# ATtiny20_Study.net
KiCad netlist of a schematic drawn in EAGLE
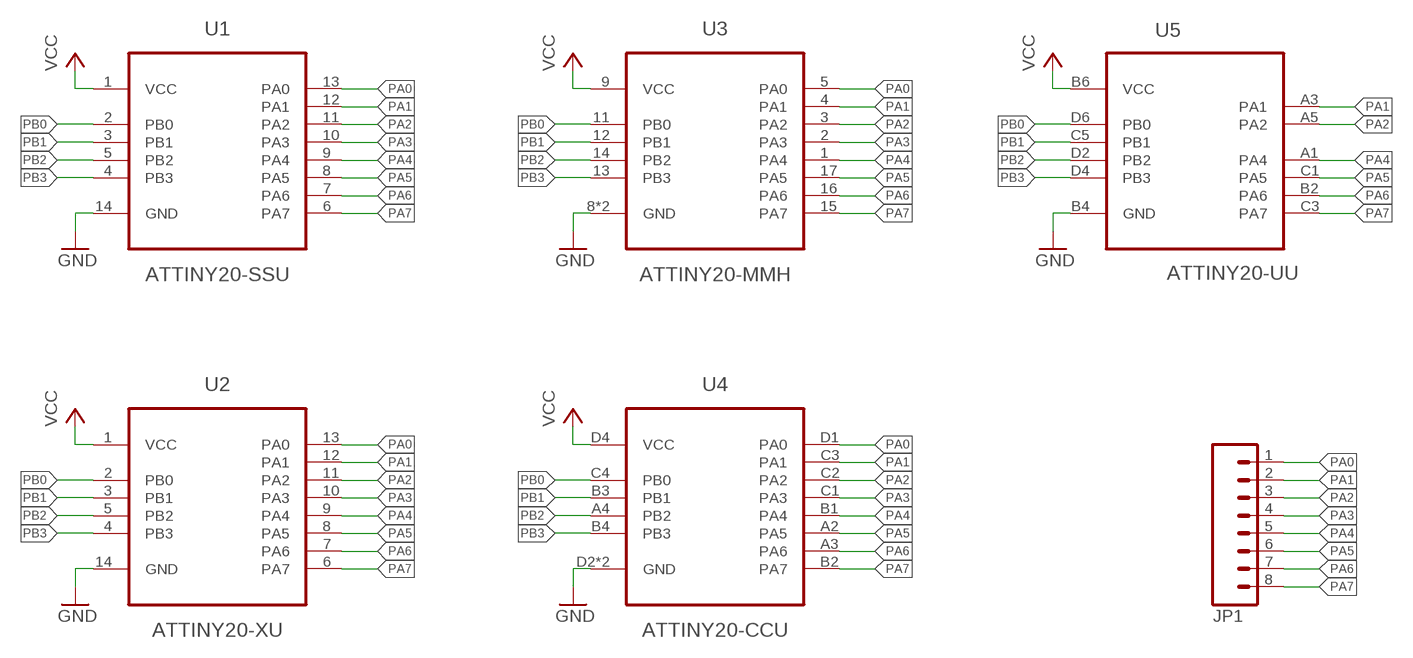
[diagram p0: schematic, sheet 1]

(export (version "E")
  (design (tool "Eeschema 10.0.6"))
  (components
    (comp (ref "JP1")
      (value "M08LOCK_NO_SILK")
      (footprint "eagle-import:1X08_LOCK_NO_SILK")
      (libsource (lib "eagle-import") (part "M08LOCK_NO_SILK"))
    )
    (comp (ref "U1")
      (value "ATTINY20-SSU")
      (footprint "eagle-import:14S1")
      (libsource (lib "eagle-import") (part "ATTINY20-SSU"))
    )
    (comp (ref "U2")
      (value "ATTINY20-XU")
      (footprint "eagle-import:14X")
      (libsource (lib "eagle-import") (part "ATTINY20-XU"))
    )
    (comp (ref "U3")
      (value "ATTINY20-MMH")
      (footprint "eagle-import:20M2")
      (libsource (lib "eagle-import") (part "ATTINY20-MMH"))
    )
    (comp (ref "U4")
      (value "ATTINY20-CCU")
      (footprint "eagle-import:15CC1")
      (libsource (lib "eagle-import") (part "ATTINY20-CCU"))
    )
    (comp (ref "U5")
      (value "ATTINY20-UU")
      (footprint "eagle-import:12U-1")
      (libsource (lib "eagle-import") (part "ATTINY20-UU"))
    )
  )
  (nets
    (net (code "1") (name "GND") (class "Default")
      (node (ref "U1") (pin "14") (pinfunction "GND_14") (pintype "passive"))
      (node (ref "U2") (pin "14") (pinfunction "GND_14") (pintype "passive"))
      (node (ref "U3") (pin "8") (pinfunction "GND_8") (pintype "passive"))
      (node (ref "U3") (pin "PAD") (pinfunction "GND_PAD") (pintype "passive"))
      (node (ref "U4") (pin "D2") (pinfunction "GND_D2") (pintype "passive"))
      (node (ref "U4") (pin "D3") (pinfunction "GND_D3") (pintype "passive"))
      (node (ref "U5") (pin "B4") (pinfunction "GND_B4") (pintype "passive"))
    )
    (net (code "2") (name "PA0") (class "Default")
      (node (ref "JP1") (pin "1") (pinfunction "1_1") (pintype "passive"))
      (node (ref "U1") (pin "13") (pinfunction "PA0_13") (pintype "bidirectional"))
      (node (ref "U2") (pin "13") (pinfunction "PA0_13") (pintype "bidirectional"))
      (node (ref "U3") (pin "5") (pinfunction "PA0_5") (pintype "bidirectional"))
      (node (ref "U4") (pin "D1") (pinfunction "PA0_D1") (pintype "bidirectional"))
    )
    (net (code "3") (name "PA1") (class "Default")
      (node (ref "JP1") (pin "2") (pinfunction "2_2") (pintype "passive"))
      (node (ref "U1") (pin "12") (pinfunction "PA1_12") (pintype "bidirectional"))
      (node (ref "U2") (pin "12") (pinfunction "PA1_12") (pintype "bidirectional"))
      (node (ref "U3") (pin "4") (pinfunction "PA1_4") (pintype "bidirectional"))
      (node (ref "U4") (pin "C3") (pinfunction "PA1_C3") (pintype "bidirectional"))
      (node (ref "U5") (pin "A3") (pinfunction "PA1_A3") (pintype "bidirectional"))
    )
    (net (code "4") (name "PA2") (class "Default")
      (node (ref "JP1") (pin "3") (pinfunction "3_3") (pintype "passive"))
      (node (ref "U1") (pin "11") (pinfunction "PA2_11") (pintype "bidirectional"))
      (node (ref "U2") (pin "11") (pinfunction "PA2_11") (pintype "bidirectional"))
      (node (ref "U3") (pin "3") (pinfunction "PA2_3") (pintype "bidirectional"))
      (node (ref "U4") (pin "C2") (pinfunction "PA2_C2") (pintype "bidirectional"))
      (node (ref "U5") (pin "A5") (pinfunction "PA2_A5") (pintype "bidirectional"))
    )
    (net (code "5") (name "PA3") (class "Default")
      (node (ref "JP1") (pin "4") (pinfunction "4_4") (pintype "passive"))
      (node (ref "U1") (pin "10") (pinfunction "PA3_10") (pintype "bidirectional"))
      (node (ref "U2") (pin "10") (pinfunction "PA3_10") (pintype "bidirectional"))
      (node (ref "U3") (pin "2") (pinfunction "PA3_2") (pintype "bidirectional"))
      (node (ref "U4") (pin "C1") (pinfunction "PA3_C1") (pintype "bidirectional"))
    )
    (net (code "6") (name "PA4") (class "Default")
      (node (ref "JP1") (pin "5") (pinfunction "5_5") (pintype "passive"))
      (node (ref "U1") (pin "9") (pinfunction "PA4_9") (pintype "bidirectional"))
      (node (ref "U2") (pin "9") (pinfunction "PA4_9") (pintype "bidirectional"))
      (node (ref "U3") (pin "1") (pinfunction "PA4_1") (pintype "bidirectional"))
      (node (ref "U4") (pin "B1") (pinfunction "PA4_B1") (pintype "bidirectional"))
      (node (ref "U5") (pin "A1") (pinfunction "PA4_A1") (pintype "bidirectional"))
    )
    (net (code "7") (name "PA5") (class "Default")
      (node (ref "JP1") (pin "6") (pinfunction "6_6") (pintype "passive"))
      (node (ref "U1") (pin "8") (pinfunction "PA5_8") (pintype "bidirectional"))
      (node (ref "U2") (pin "8") (pinfunction "PA5_8") (pintype "bidirectional"))
      (node (ref "U3") (pin "17") (pinfunction "PA5_17") (pintype "bidirectional"))
      (node (ref "U4") (pin "A2") (pinfunction "PA5_A2") (pintype "bidirectional"))
      (node (ref "U5") (pin "C1") (pinfunction "PA5_C1") (pintype "bidirectional"))
    )
    (net (code "8") (name "PA6") (class "Default")
      (node (ref "JP1") (pin "7") (pinfunction "7_7") (pintype "passive"))
      (node (ref "U1") (pin "7") (pinfunction "PA6_7") (pintype "bidirectional"))
      (node (ref "U2") (pin "7") (pinfunction "PA6_7") (pintype "bidirectional"))
      (node (ref "U3") (pin "16") (pinfunction "PA6_16") (pintype "bidirectional"))
      (node (ref "U4") (pin "A3") (pinfunction "PA6_A3") (pintype "bidirectional"))
      (node (ref "U5") (pin "B2") (pinfunction "PA6_B2") (pintype "bidirectional"))
    )
    (net (code "9") (name "PA7") (class "Default")
      (node (ref "JP1") (pin "8") (pinfunction "8_8") (pintype "passive"))
      (node (ref "U1") (pin "6") (pinfunction "PA7_6") (pintype "bidirectional"))
      (node (ref "U2") (pin "6") (pinfunction "PA7_6") (pintype "bidirectional"))
      (node (ref "U3") (pin "15") (pinfunction "PA7_15") (pintype "bidirectional"))
      (node (ref "U4") (pin "B2") (pinfunction "PA7_B2") (pintype "bidirectional"))
      (node (ref "U5") (pin "C3") (pinfunction "PA7_C3") (pintype "bidirectional"))
    )
    (net (code "10") (name "PB0") (class "Default")
      (node (ref "U1") (pin "2") (pinfunction "PB0_2") (pintype "bidirectional"))
      (node (ref "U2") (pin "2") (pinfunction "PB0_2") (pintype "bidirectional"))
      (node (ref "U3") (pin "11") (pinfunction "PB0_11") (pintype "bidirectional"))
      (node (ref "U4") (pin "C4") (pinfunction "PB0_C4") (pintype "bidirectional"))
      (node (ref "U5") (pin "D6") (pinfunction "PB0_D6") (pintype "bidirectional"))
    )
    (net (code "11") (name "PB1") (class "Default")
      (node (ref "U1") (pin "3") (pinfunction "PB1_3") (pintype "bidirectional"))
      (node (ref "U2") (pin "3") (pinfunction "PB1_3") (pintype "bidirectional"))
      (node (ref "U3") (pin "12") (pinfunction "PB1_12") (pintype "bidirectional"))
      (node (ref "U4") (pin "B3") (pinfunction "PB1_B3") (pintype "bidirectional"))
      (node (ref "U5") (pin "C5") (pinfunction "PB1_C5") (pintype "bidirectional"))
    )
    (net (code "12") (name "PB2") (class "Default")
      (node (ref "U1") (pin "5") (pinfunction "PB2_5") (pintype "bidirectional"))
      (node (ref "U2") (pin "5") (pinfunction "PB2_5") (pintype "bidirectional"))
      (node (ref "U3") (pin "14") (pinfunction "PB2_14") (pintype "bidirectional"))
      (node (ref "U4") (pin "A4") (pinfunction "PB2_A4") (pintype "bidirectional"))
      (node (ref "U5") (pin "D2") (pinfunction "PB2_D2") (pintype "bidirectional"))
    )
    (net (code "13") (name "PB3") (class "Default")
      (node (ref "U1") (pin "4") (pinfunction "PB3_4") (pintype "bidirectional"))
      (node (ref "U2") (pin "4") (pinfunction "PB3_4") (pintype "bidirectional"))
      (node (ref "U3") (pin "13") (pinfunction "PB3_13") (pintype "bidirectional"))
      (node (ref "U4") (pin "B4") (pinfunction "PB3_B4") (pintype "bidirectional"))
      (node (ref "U5") (pin "D4") (pinfunction "PB3_D4") (pintype "bidirectional"))
    )
    (net (code "14") (name "VCC") (class "Default")
      (node (ref "U1") (pin "1") (pinfunction "VCC_1") (pintype "power_in"))
      (node (ref "U2") (pin "1") (pinfunction "VCC_1") (pintype "power_in"))
      (node (ref "U3") (pin "9") (pinfunction "VCC_9") (pintype "power_in"))
      (node (ref "U4") (pin "D4") (pinfunction "VCC_D4") (pintype "power_in"))
      (node (ref "U5") (pin "B6") (pinfunction "VCC_B6") (pintype "power_in"))
    )
  )
)
